# SCH_MY-first-PCB_2026-09-03.net
KiCad netlist of a schematic drawn in EasyEDA
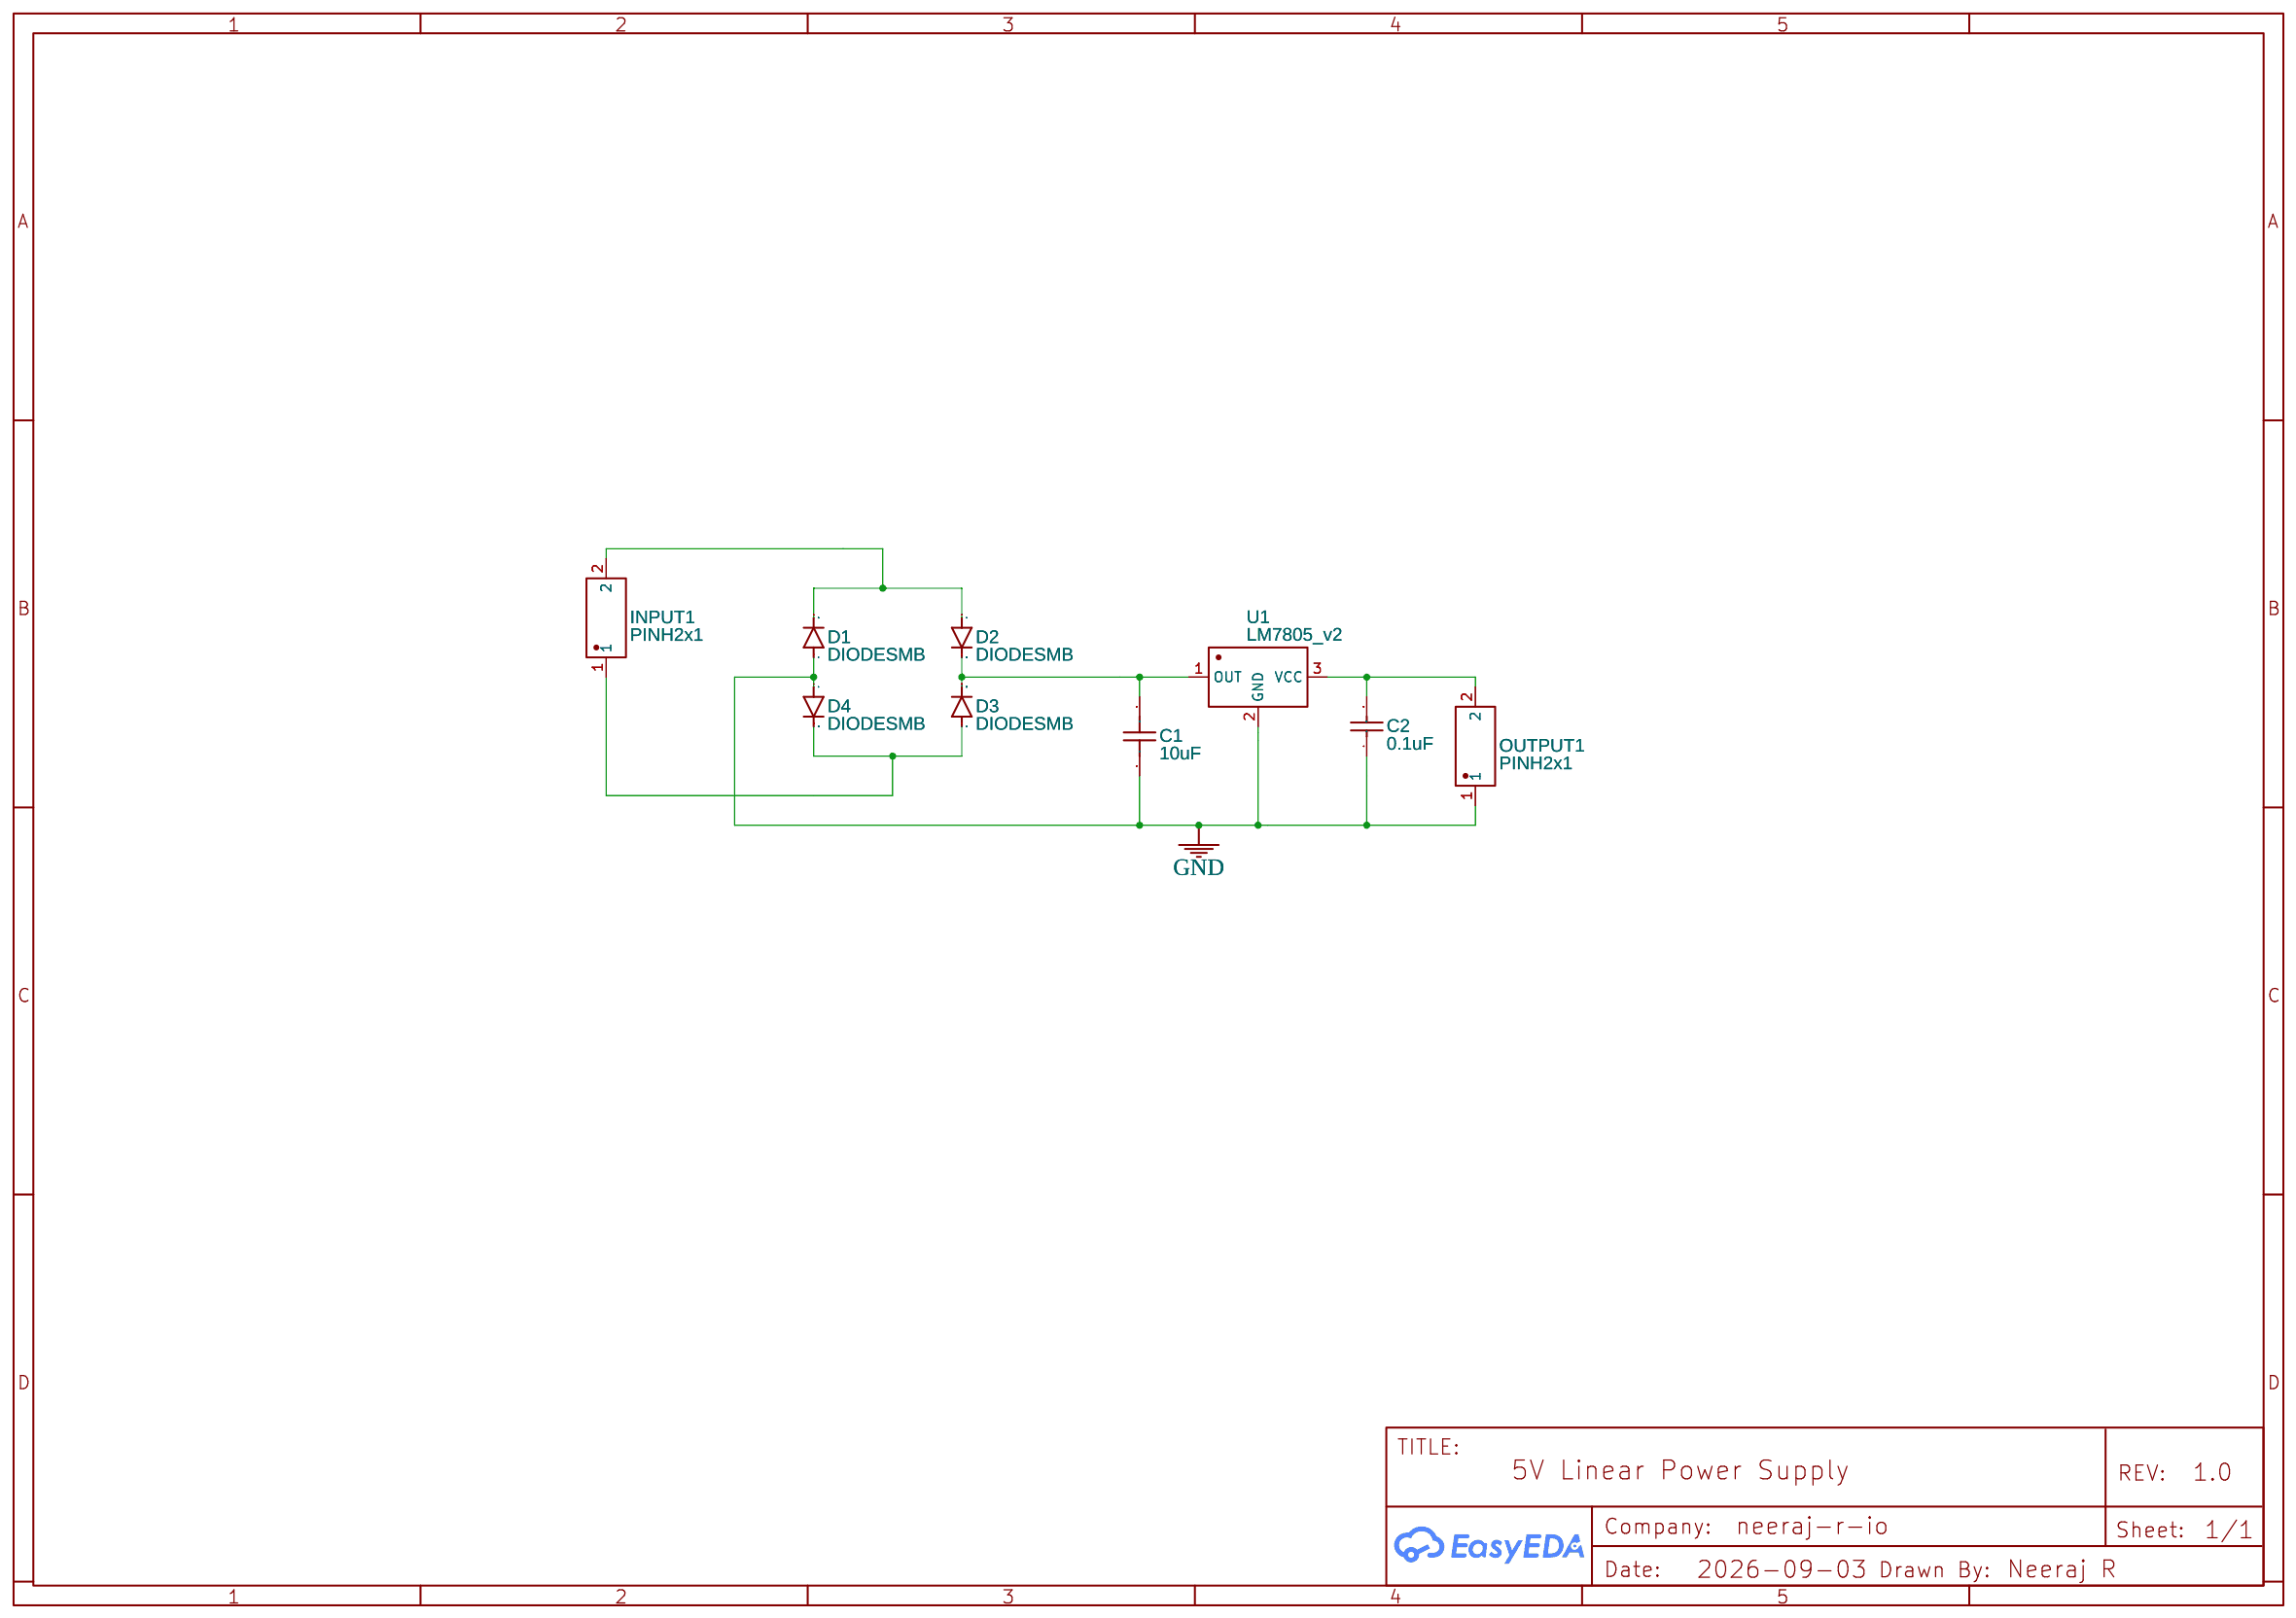
[diagram p0: schematic sheet]

(export (version "E")
  (design (tool "Eeschema 10.0.6"))
  (components
    (comp (ref "C1") (value "10uF") (libsource (lib "") (part "C_0603_US")))
    (comp (ref "C2")
      (value "0.1uF")
      (fields (field (name "Manufacturer Part") "Capacitor15nf100v") (field (name "Manufacturer") "ReliaPro"))
      (libsource (lib "") (part "CAPACITOR-0.1uF-400V"))
    )
    (comp (ref "D1") (value "DIODESMB") (libsource (lib "") (part "DIODESMB")))
    (comp (ref "D2") (value "DIODESMB") (libsource (lib "") (part "DIODESMB_1")))
    (comp (ref "D3") (value "DIODESMB") (libsource (lib "") (part "DIODESMB")))
    (comp (ref "D4") (value "DIODESMB") (libsource (lib "") (part "DIODESMB_1")))
    (comp (ref "INPUT1") (value "PINH2x1") (libsource (lib "") (part "PINH2x1")))
    (comp (ref "OUTPUT1") (value "PINH2x1") (libsource (lib "") (part "PINH2x1_1")))
    (comp (ref "U1") (value "LM7805_v2") (libsource (lib "") (part "LM7805_v2")))
  )
  (nets
    (net (code "1") (name "GND") (class "Default")
      (node (ref "C1") (pin "2") (pinfunction "2_2") (pintype "unspecified"))
      (node (ref "C2") (pin "1") (pinfunction "1_1") (pintype "unspecified"))
      (node (ref "D1") (pin "A") (pinfunction "A_A") (pintype "unspecified"))
      (node (ref "D4") (pin "A") (pinfunction "A_A") (pintype "unspecified"))
      (node (ref "OUTPUT1") (pin "1") (pinfunction "1_1") (pintype "unspecified"))
      (node (ref "U1") (pin "2") (pinfunction "GND_2") (pintype "unspecified"))
    )
    (net (code "2") (name "Net-(D1-PadC)") (class "Default")
      (node (ref "D1") (pin "C") (pinfunction "C_C") (pintype "unspecified"))
      (node (ref "D2") (pin "A") (pinfunction "A_A") (pintype "unspecified"))
      (node (ref "INPUT1") (pin "2") (pinfunction "2_2") (pintype "unspecified"))
    )
    (net (code "3") (name "Net-(D3-PadA)") (class "Default")
      (node (ref "D3") (pin "A") (pinfunction "A_A") (pintype "unspecified"))
      (node (ref "D4") (pin "C") (pinfunction "C_C") (pintype "unspecified"))
      (node (ref "INPUT1") (pin "1") (pinfunction "1_1") (pintype "unspecified"))
    )
    (net (code "4") (name "Net-(U1-OUT)") (class "Default")
      (node (ref "C1") (pin "1") (pinfunction "1_1") (pintype "unspecified"))
      (node (ref "D2") (pin "C") (pinfunction "C_C") (pintype "unspecified"))
      (node (ref "D3") (pin "C") (pinfunction "C_C") (pintype "unspecified"))
      (node (ref "U1") (pin "1") (pinfunction "OUT_1") (pintype "unspecified"))
    )
    (net (code "5") (name "Net-(U1-VCC)") (class "Default")
      (node (ref "C2") (pin "2") (pinfunction "2_2") (pintype "unspecified"))
      (node (ref "OUTPUT1") (pin "2") (pinfunction "2_2") (pintype "unspecified"))
      (node (ref "U1") (pin "3") (pinfunction "VCC_3") (pintype "unspecified"))
    )
  )
)
